# ProPrj__G__2025-08-02.net
KiCad netlist of a schematic drawn in EasyEDA Pro
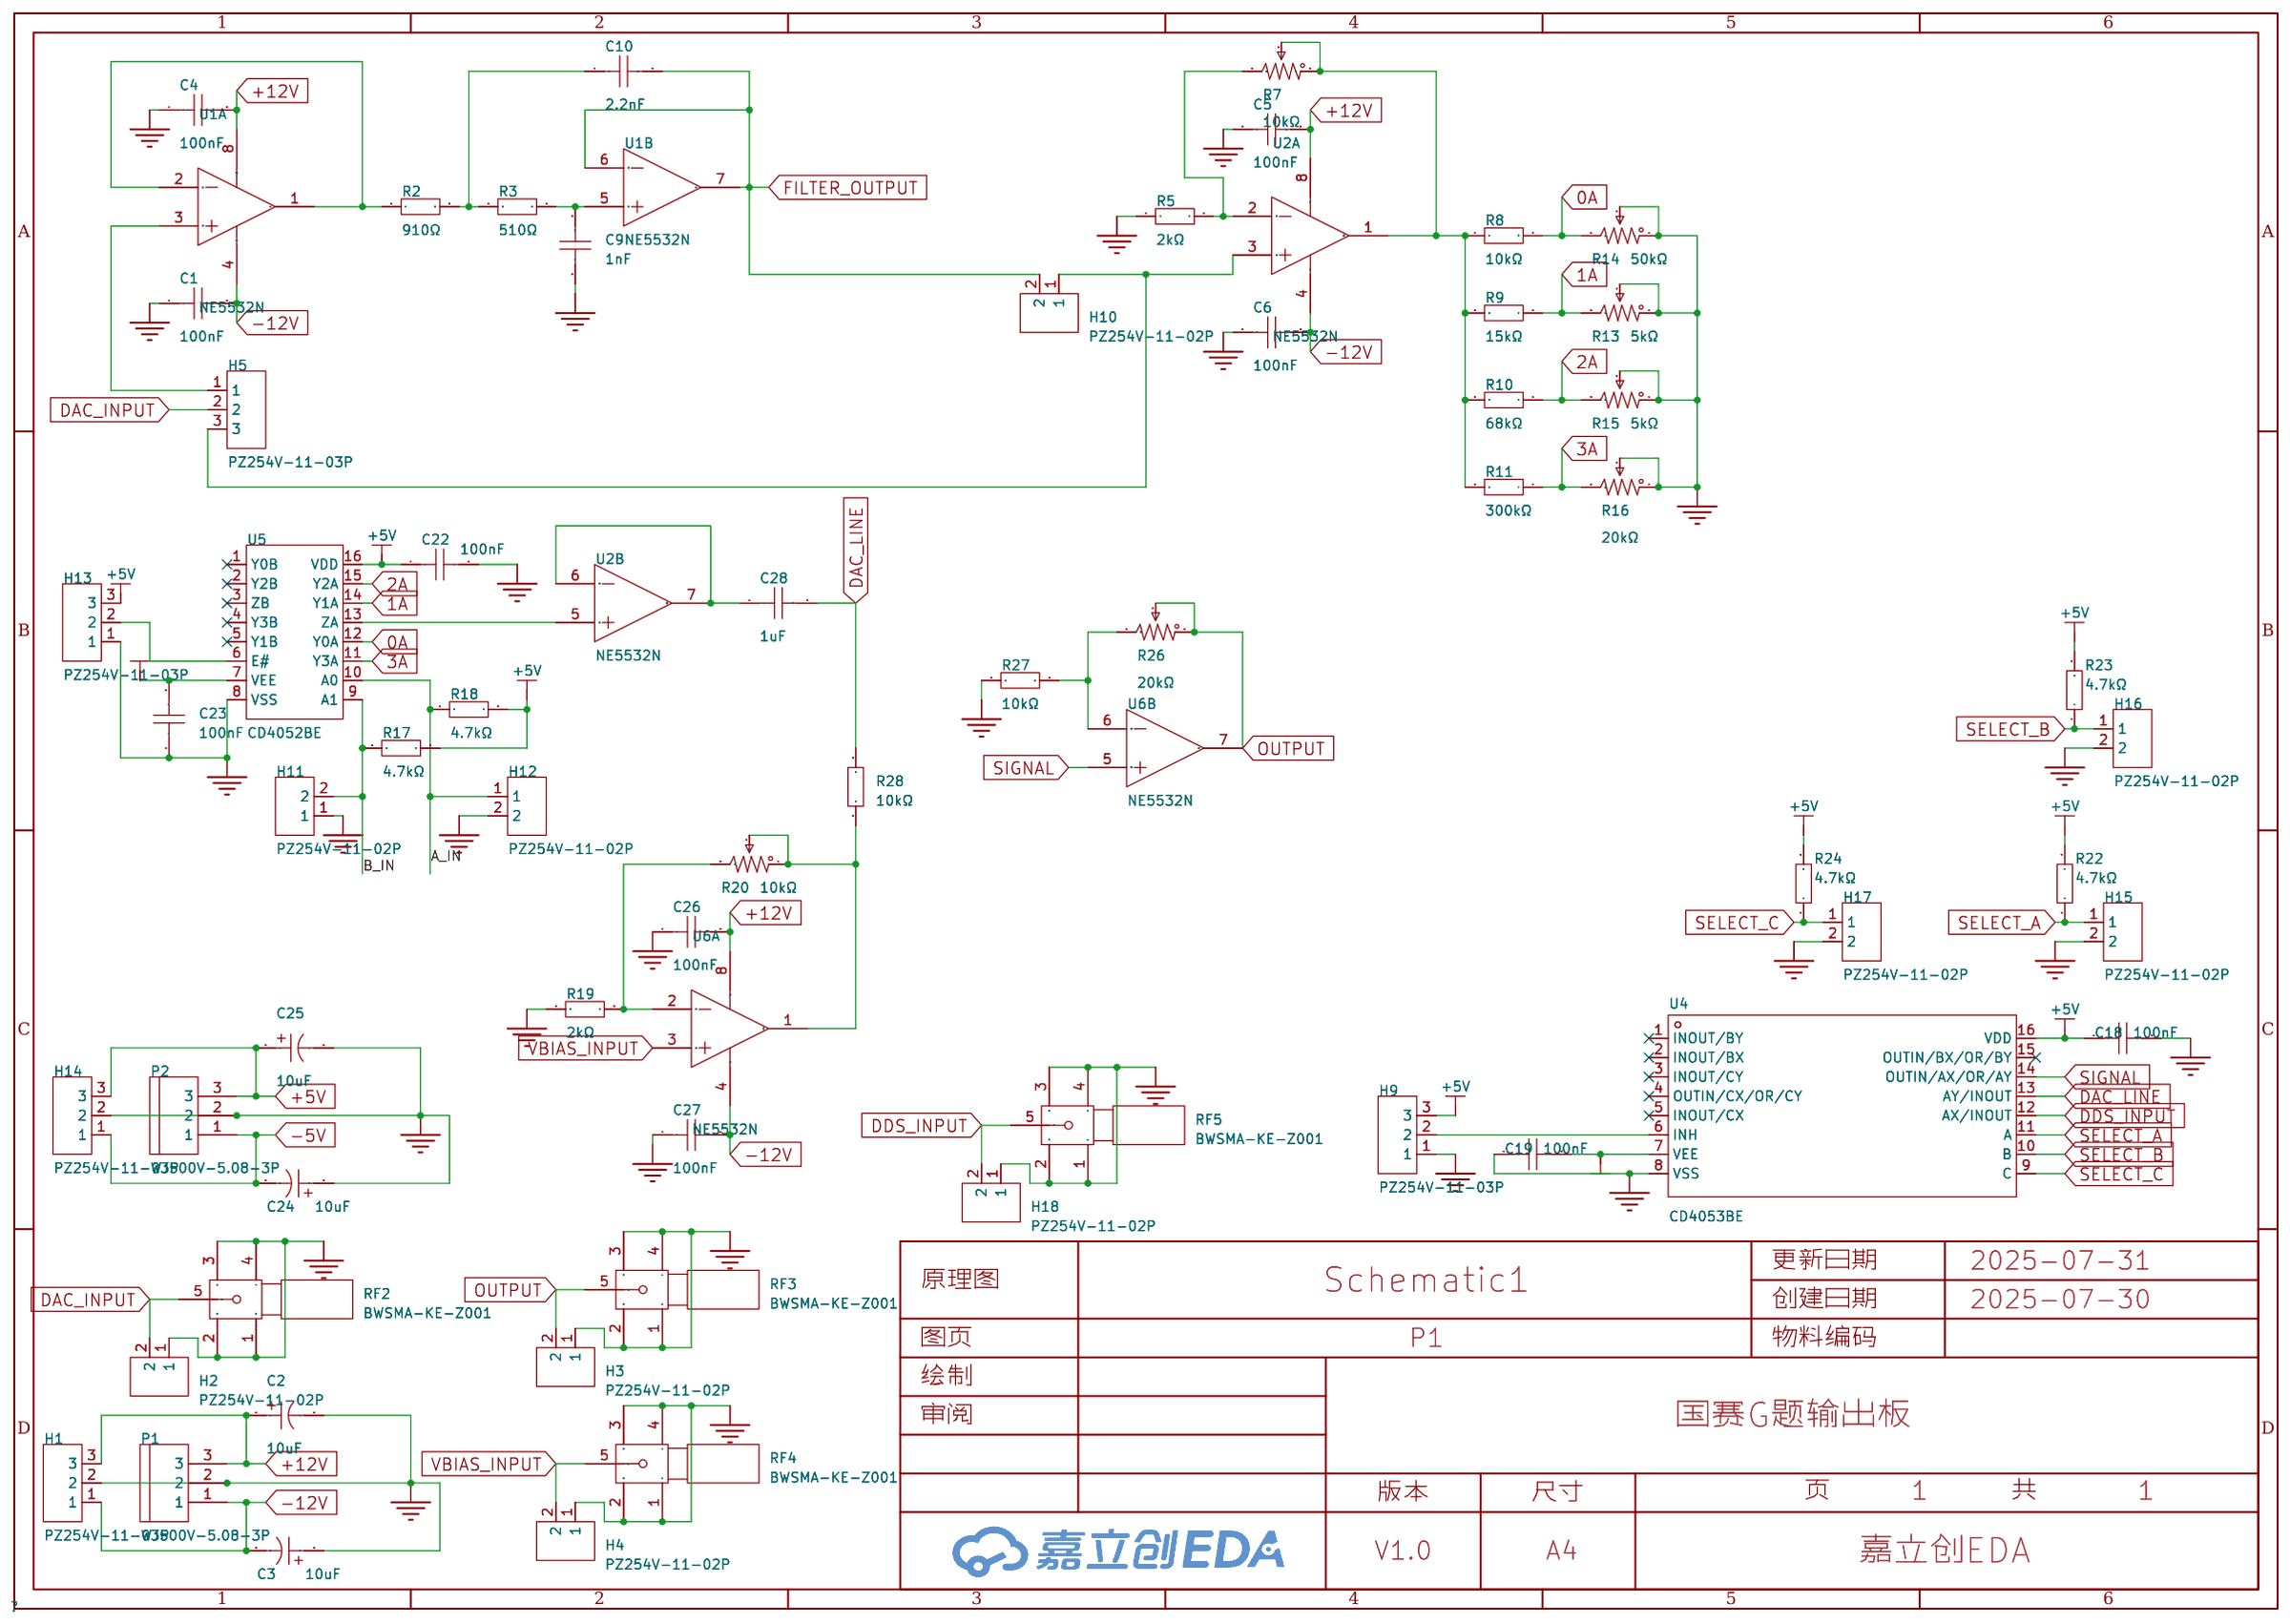
[diagram p0: schematic sheet]

(export (version "E")
  (design (tool "Eeschema 10.0.6"))
  (components
    (comp (ref "C1")
      (value "100nF")
      (footprint "easyedapro:CAP-TH_L5.8-W2.4-P2.54-D0.6")
      (description "容值:100nF;精度:-20%~+80%;额定电压:50V;温度系数:Y5V;")
      (fields
        (field (name "Manufacturer Part") "CC1H104ZA1ED3F5P1100")
        (field (name "Manufacturer") "Dersonic(德尔创)")
      )
      (libsource (lib "easyedapro") (part "CC1H104ZA1ED3F5P1100"))
    )
    (comp (ref "C2")
      (value "10uF")
      (fields (field (name "Manufacturer Part") "ERG450V10M10x16") (field (name "Manufacturer") "捷而瑞"))
      (libsource (lib "easyedapro") (part "ERG25V10M5X11"))
    )
    (comp (ref "C3")
      (value "10uF")
      (fields (field (name "Manufacturer Part") "ERG450V10M10x16") (field (name "Manufacturer") "捷而瑞"))
      (libsource (lib "easyedapro") (part "ERG25V10M5X11"))
    )
    (comp (ref "C4")
      (value "100nF")
      (footprint "easyedapro:CAP-TH_L5.8-W2.4-P2.54-D0.6")
      (description "容值:100nF;精度:-20%~+80%;额定电压:50V;温度系数:Y5V;")
      (fields
        (field (name "Manufacturer Part") "CC1H104ZA1ED3F5P1100")
        (field (name "Manufacturer") "Dersonic(德尔创)")
      )
      (libsource (lib "easyedapro") (part "CC1H104ZA1ED3F5P1100"))
    )
    (comp (ref "C5")
      (value "100nF")
      (footprint "easyedapro:CAP-TH_L5.8-W2.4-P2.54-D0.6")
      (description "容值:100nF;精度:-20%~+80%;额定电压:50V;温度系数:Y5V;")
      (fields
        (field (name "Manufacturer Part") "CC1H104ZA1ED3F5P1100")
        (field (name "Manufacturer") "Dersonic(德尔创)")
      )
      (libsource (lib "easyedapro") (part "CC1H104ZA1ED3F5P1100"))
    )
    (comp (ref "C6")
      (value "100nF")
      (footprint "easyedapro:CAP-TH_L5.8-W2.4-P2.54-D0.6")
      (description "容值:100nF;精度:-20%~+80%;额定电压:50V;温度系数:Y5V;")
      (fields
        (field (name "Manufacturer Part") "CC1H104ZA1ED3F5P1100")
        (field (name "Manufacturer") "Dersonic(德尔创)")
      )
      (libsource (lib "easyedapro") (part "CC1H104ZA1ED3F5P1100"))
    )
    (comp (ref "C9")
      (value "1nF")
      (footprint "easyedapro:CAP-TH_L6.8-W2.6-P5.08-D0.6-S2.1")
      (description "容值:1nF;精度:±10%;额定电压:2kV;温度系数:Y5P;")
      (fields
        (field (name "Manufacturer Part") "CC3D102KC2IEB46U31MF")
        (field (name "Manufacturer") "Dersonic(德尔创)")
      )
      (libsource (lib "easyedapro") (part "CC3D102KC2IEB46U31MF"))
    )
    (comp (ref "C10")
      (value "2.2nF")
      (footprint "easyedapro:CAP-TH_L6.0-W3.0-P5.00-D1.0")
      (description "容值:2.2nF;精度:±20%;额定电压:2kV;温度系数:Y5V;")
      (fields (field (name "Manufacturer Part") "R06F1B222MN0B0S0N0") (field (name "Manufacturer") "STE(松田)"))
      (libsource (lib "easyedapro") (part "R06F1B222MN0B0S0N0"))
    )
    (comp (ref "C18")
      (value "100nF")
      (footprint "easyedapro:CAP-TH_L5.0-W2.5-P5.00-D1.0")
      (description "容值:100nF;精度:±20%;额定电压:50V;温度系数:Y5V;")
      (fields
        (field (name "Manufacturer Part") "CC1H104MC1FD3F6C10MF")
        (field (name "Manufacturer") "Dersonic(德尔创)")
      )
      (libsource (lib "easyedapro") (part "CC1H104MC1FD3F6C10MF"))
    )
    (comp (ref "C19")
      (value "100nF")
      (footprint "easyedapro:CAP-TH_L5.0-W2.5-P5.00-D1.0")
      (description "容值:100nF;精度:±20%;额定电压:50V;温度系数:Y5V;")
      (fields
        (field (name "Manufacturer Part") "CC1H104MC1FD3F6C10MF")
        (field (name "Manufacturer") "Dersonic(德尔创)")
      )
      (libsource (lib "easyedapro") (part "CC1H104MC1FD3F6C10MF"))
    )
    (comp (ref "C22")
      (value "100nF")
      (footprint "easyedapro:CAP-TH_L5.8-W2.4-P2.54-D0.6")
      (description "容值:100nF;精度:-20%~+80%;额定电压:50V;温度系数:Y5V;")
      (fields
        (field (name "Manufacturer Part") "CC1H104ZA1ED3F5P1100")
        (field (name "Manufacturer") "Dersonic(德尔创)")
      )
      (libsource (lib "easyedapro") (part "CC1H104ZA1ED3F5P1100"))
    )
    (comp (ref "C23")
      (value "100nF")
      (footprint "easyedapro:CAP-TH_L5.8-W2.4-P2.54-D0.6")
      (description "容值:100nF;精度:-20%~+80%;额定电压:50V;温度系数:Y5V;")
      (fields
        (field (name "Manufacturer Part") "CC1H104ZA1ED3F5P1100")
        (field (name "Manufacturer") "Dersonic(德尔创)")
      )
      (libsource (lib "easyedapro") (part "CC1H104ZA1ED3F5P1100"))
    )
    (comp (ref "C24")
      (value "10uF")
      (fields (field (name "Manufacturer Part") "ERG450V10M10x16") (field (name "Manufacturer") "捷而瑞"))
      (libsource (lib "easyedapro") (part "ERG25V10M5X11"))
    )
    (comp (ref "C25")
      (value "10uF")
      (fields (field (name "Manufacturer Part") "ERG450V10M10x16") (field (name "Manufacturer") "捷而瑞"))
      (libsource (lib "easyedapro") (part "ERG25V10M5X11"))
    )
    (comp (ref "C26")
      (value "100nF")
      (footprint "easyedapro:CAP-TH_L5.8-W2.4-P2.54-D0.6")
      (description "容值:100nF;精度:-20%~+80%;额定电压:50V;温度系数:Y5V;")
      (fields
        (field (name "Manufacturer Part") "CC1H104ZA1ED3F5P1100")
        (field (name "Manufacturer") "Dersonic(德尔创)")
      )
      (libsource (lib "easyedapro") (part "CC1H104ZA1ED3F5P1100"))
    )
    (comp (ref "C27")
      (value "100nF")
      (footprint "easyedapro:CAP-TH_L5.8-W2.4-P2.54-D0.6")
      (description "容值:100nF;精度:-20%~+80%;额定电压:50V;温度系数:Y5V;")
      (fields
        (field (name "Manufacturer Part") "CC1H104ZA1ED3F5P1100")
        (field (name "Manufacturer") "Dersonic(德尔创)")
      )
      (libsource (lib "easyedapro") (part "CC1H104ZA1ED3F5P1100"))
    )
    (comp (ref "C28")
      (value "1uF")
      (footprint "easyedapro:CAP-TH_L5.5-W3.5-P5.00-D1.2")
      (description "容值:1uF;精度:±10%;额定电压:50V;温度系数:X7R;")
      (fields (field (name "Manufacturer Part") "FK26X7R1H105KRE06") (field (name "Manufacturer") "TDK"))
      (libsource (lib "easyedapro") (part "FK26X7R1H105KRE06"))
    )
    (comp (ref "H1")
      (value "PZ254V-11-03P")
      (footprint "easyedapro:HDR-TH_3P-P2.54-V-M")
      (fields (field (name "Manufacturer") "XFCN(兴飞)"))
      (libsource (lib "easyedapro") (part "PZ254V-11-03P_C2937625"))
    )
    (comp (ref "H2")
      (value "PZ254V-11-02P")
      (footprint "easyedapro:HDR-TH_2P-P2.54-V-M")
      (fields (field (name "Manufacturer") "XFCN(兴飞)"))
      (libsource (lib "easyedapro") (part "PZ254V-11-02P"))
    )
    (comp (ref "H3")
      (value "PZ254V-11-02P")
      (footprint "easyedapro:HDR-TH_2P-P2.54-V-M")
      (fields (field (name "Manufacturer") "XFCN(兴飞)"))
      (libsource (lib "easyedapro") (part "PZ254V-11-02P"))
    )
    (comp (ref "H4")
      (value "PZ254V-11-02P")
      (footprint "easyedapro:HDR-TH_2P-P2.54-V-M")
      (fields (field (name "Manufacturer") "XFCN(兴飞)"))
      (libsource (lib "easyedapro") (part "PZ254V-11-02P"))
    )
    (comp (ref "H5")
      (value "PZ254V-11-03P")
      (footprint "easyedapro:HDR-TH_3P-P2.54-V-M")
      (fields (field (name "Manufacturer") "XFCN(兴飞)"))
      (libsource (lib "easyedapro") (part "PZ254V-11-03P_C2937625"))
    )
    (comp (ref "H9")
      (value "PZ254V-11-03P")
      (footprint "easyedapro:HDR-TH_3P-P2.54-V-M")
      (fields (field (name "Manufacturer") "XFCN(兴飞)"))
      (libsource (lib "easyedapro") (part "PZ254V-11-03P_C2937625"))
    )
    (comp (ref "H10")
      (value "PZ254V-11-02P")
      (footprint "easyedapro:HDR-TH_2P-P2.54-V-M")
      (fields (field (name "Manufacturer") "XFCN(兴飞)"))
      (libsource (lib "easyedapro") (part "PZ254V-11-02P"))
    )
    (comp (ref "H11")
      (value "PZ254V-11-02P")
      (footprint "easyedapro:HDR-TH_2P-P2.54-V-M")
      (fields (field (name "Manufacturer") "XFCN(兴飞)"))
      (libsource (lib "easyedapro") (part "PZ254V-11-02P"))
    )
    (comp (ref "H12")
      (value "PZ254V-11-02P")
      (footprint "easyedapro:HDR-TH_2P-P2.54-V-M")
      (fields (field (name "Manufacturer") "XFCN(兴飞)"))
      (libsource (lib "easyedapro") (part "PZ254V-11-02P"))
    )
    (comp (ref "H13")
      (value "PZ254V-11-03P")
      (footprint "easyedapro:HDR-TH_3P-P2.54-V-M")
      (fields (field (name "Manufacturer") "XFCN(兴飞)"))
      (libsource (lib "easyedapro") (part "PZ254V-11-03P_C2937625"))
    )
    (comp (ref "H14")
      (value "PZ254V-11-03P")
      (footprint "easyedapro:HDR-TH_3P-P2.54-V-M")
      (fields (field (name "Manufacturer") "XFCN(兴飞)"))
      (libsource (lib "easyedapro") (part "PZ254V-11-03P_C2937625"))
    )
    (comp (ref "H15")
      (value "PZ254V-11-02P")
      (footprint "easyedapro:HDR-TH_2P-P2.54-V-M")
      (fields (field (name "Manufacturer") "XFCN(兴飞)"))
      (libsource (lib "easyedapro") (part "PZ254V-11-02P"))
    )
    (comp (ref "H16")
      (value "PZ254V-11-02P")
      (footprint "easyedapro:HDR-TH_2P-P2.54-V-M")
      (fields (field (name "Manufacturer") "XFCN(兴飞)"))
      (libsource (lib "easyedapro") (part "PZ254V-11-02P"))
    )
    (comp (ref "H17")
      (value "PZ254V-11-02P")
      (footprint "easyedapro:HDR-TH_2P-P2.54-V-M")
      (fields (field (name "Manufacturer") "XFCN(兴飞)"))
      (libsource (lib "easyedapro") (part "PZ254V-11-02P"))
    )
    (comp (ref "H18")
      (value "PZ254V-11-02P")
      (footprint "easyedapro:HDR-TH_2P-P2.54-V-M")
      (fields (field (name "Manufacturer") "XFCN(兴飞)"))
      (libsource (lib "easyedapro") (part "PZ254V-11-02P"))
    )
    (comp (ref "P1")
      (value "WJ500V-5.08-3P")
      (footprint "easyedapro:CONN-TH_3P-P5.00_WJ500V-5.08-3P")
      (fields (field (name "Manufacturer") "KANGNEX(康奈克斯电气)"))
      (libsource (lib "easyedapro") (part "WJ500V-5.08-3P-14-00A"))
    )
    (comp (ref "P2")
      (value "WJ500V-5.08-3P")
      (footprint "easyedapro:CONN-TH_3P-P5.00_WJ500V-5.08-3P")
      (fields (field (name "Manufacturer") "KANGNEX(康奈克斯电气)"))
      (libsource (lib "easyedapro") (part "WJ500V-5.08-3P-14-00A"))
    )
    (comp (ref "R2")
      (value "910Ω")
      (footprint "easyedapro:Res_1/8W")
      (libsource (lib "easyedapro") (part "电阻"))
    )
    (comp (ref "R3")
      (value "510Ω")
      (footprint "easyedapro:Res_1/8W")
      (libsource (lib "easyedapro") (part "电阻"))
    )
    (comp (ref "R5")
      (value "2kΩ")
      (footprint "easyedapro:Res_1/8W")
      (libsource (lib "easyedapro") (part "电阻"))
    )
    (comp (ref "R7")
      (value "10kΩ")
      (footprint "easyedapro:RES-ADJ-TH_3P-L10.0-W10.0-P2.50-L")
      (description "阻值:10kΩ;精度:±10%;")
      (fields (field (name "Manufacturer Part") "3296W-1-103") (field (name "Manufacturer") "BOCHEN(博晨)"))
      (libsource (lib "easyedapro") (part "3296W-1-103"))
    )
    (comp (ref "R8")
      (value "10kΩ")
      (footprint "easyedapro:Res_1/8W")
      (libsource (lib "easyedapro") (part "电阻"))
    )
    (comp (ref "R9")
      (value "15kΩ")
      (footprint "easyedapro:Res_1/8W")
      (libsource (lib "easyedapro") (part "电阻"))
    )
    (comp (ref "R10")
      (value "68kΩ")
      (footprint "easyedapro:Res_1/8W")
      (libsource (lib "easyedapro") (part "电阻"))
    )
    (comp (ref "R11")
      (value "300kΩ")
      (footprint "easyedapro:Res_1/8W")
      (libsource (lib "easyedapro") (part "电阻"))
    )
    (comp (ref "R13")
      (value "5kΩ")
      (footprint "easyedapro:RES-ADJ-TH_3P-L9.5-W4.85-P2.50-BL-BS")
      (description "阻值:5kΩ;精度:±10%;")
      (fields (field (name "Manufacturer Part") "3296W-1-502") (field (name "Manufacturer") "BOCHEN(博晨)"))
      (libsource (lib "easyedapro") (part "3296W-1-502"))
    )
    (comp (ref "R14")
      (value "50kΩ")
      (footprint "easyedapro:RES-ADJ-TH_3P-L9.5-W4.85-P2.50-BL-BS")
      (description "阻值:50kΩ;精度:±10%;")
      (fields (field (name "Manufacturer Part") "3296W-1-503") (field (name "Manufacturer") "BOCHEN(博晨)"))
      (libsource (lib "easyedapro") (part "3296W-1-503"))
    )
    (comp (ref "R15")
      (value "5kΩ")
      (footprint "easyedapro:RES-ADJ-TH_3P-L9.5-W4.85-P2.50-BL-BS")
      (description "阻值:5kΩ;精度:±10%;")
      (fields (field (name "Manufacturer Part") "3296W-1-502") (field (name "Manufacturer") "BOCHEN(博晨)"))
      (libsource (lib "easyedapro") (part "3296W-1-502"))
    )
    (comp (ref "R16")
      (value "20kΩ")
      (footprint "easyedapro:RES-ADJ-TH_3P-L10.0-W10.0-P2.50-BL-BS")
      (description "阻值:20kΩ;精度:±10%;")
      (fields (field (name "Manufacturer Part") "3296W-1-203") (field (name "Manufacturer") "BOCHEN(博晨)"))
      (libsource (lib "easyedapro") (part "3296W-1-203"))
    )
    (comp (ref "R17")
      (value "4.7kΩ")
      (footprint "easyedapro:Res_1/8W")
      (libsource (lib "easyedapro") (part "电阻"))
    )
    (comp (ref "R18")
      (value "4.7kΩ")
      (footprint "easyedapro:Res_1/8W")
      (libsource (lib "easyedapro") (part "电阻"))
    )
    (comp (ref "R19")
      (value "2kΩ")
      (footprint "easyedapro:Res_1/8W")
      (libsource (lib "easyedapro") (part "电阻"))
    )
    (comp (ref "R20")
      (value "10kΩ")
      (footprint "easyedapro:RES-ADJ-TH_3P-L10.0-W10.0-P2.50-L")
      (description "阻值:10kΩ;精度:±10%;")
      (fields (field (name "Manufacturer Part") "3296W-1-103") (field (name "Manufacturer") "BOCHEN(博晨)"))
      (libsource (lib "easyedapro") (part "3296W-1-103"))
    )
    (comp (ref "R22")
      (value "4.7kΩ")
      (footprint "easyedapro:Res_1/8W")
      (libsource (lib "easyedapro") (part "电阻"))
    )
    (comp (ref "R23")
      (value "4.7kΩ")
      (footprint "easyedapro:Res_1/8W")
      (libsource (lib "easyedapro") (part "电阻"))
    )
    (comp (ref "R24")
      (value "4.7kΩ")
      (footprint "easyedapro:Res_1/8W")
      (libsource (lib "easyedapro") (part "电阻"))
    )
    (comp (ref "R26")
      (value "20kΩ")
      (footprint "easyedapro:RES-ADJ-TH_3P-L10.0-W10.0-P2.50-BL-BS")
      (description "阻值:20kΩ;精度:±10%;")
      (fields (field (name "Manufacturer Part") "3296W-1-203") (field (name "Manufacturer") "BOCHEN(博晨)"))
      (libsource (lib "easyedapro") (part "3296W-1-203"))
    )
    (comp (ref "R27")
      (value "10kΩ")
      (footprint "easyedapro:Res_1/8W")
      (libsource (lib "easyedapro") (part "电阻"))
    )
    (comp (ref "R28")
      (value "10kΩ")
      (footprint "easyedapro:Res_1/8W")
      (libsource (lib "easyedapro") (part "电阻"))
    )
    (comp (ref "RF2")
      (value "BWSMA-KE-Z001")
      (footprint "easyedapro:SMA-TH_BWSMA-KE-Z001")
      (fields (field (name "Manufacturer") "BAT WIRELESS(蝙蝠无线)"))
      (libsource (lib "easyedapro") (part "BWSMA-KE-Z001"))
    )
    (comp (ref "RF3")
      (value "BWSMA-KE-Z001")
      (footprint "easyedapro:SMA-TH_BWSMA-KE-Z001")
      (fields (field (name "Manufacturer") "BAT WIRELESS(蝙蝠无线)"))
      (libsource (lib "easyedapro") (part "BWSMA-KE-Z001"))
    )
    (comp (ref "RF4")
      (value "BWSMA-KE-Z001")
      (footprint "easyedapro:SMA-TH_BWSMA-KE-Z001")
      (fields (field (name "Manufacturer") "BAT WIRELESS(蝙蝠无线)"))
      (libsource (lib "easyedapro") (part "BWSMA-KE-Z001"))
    )
    (comp (ref "RF5")
      (value "BWSMA-KE-Z001")
      (footprint "easyedapro:SMA-TH_BWSMA-KE-Z001")
      (fields (field (name "Manufacturer") "BAT WIRELESS(蝙蝠无线)"))
      (libsource (lib "easyedapro") (part "BWSMA-KE-Z001"))
    )
    (comp (ref "U1")
      (value "NE5532N")
      (footprint "easyedapro:DIP-8_L9.3-W6.4-P2.54-LS7.6-BL")
      (description "放大器数:双路;轨到轨:-;增益带宽积(GBP):10MHz;输入失调电压(Vos):5mV;压摆率(SR):11V/us;输入偏置电流(Ib):500nA;")
      (fields (field (name "Manufacturer") "HGSEMI(华冠)"))
      (libsource (lib "easyedapro") (part "NE5532N"))
    )
    (comp (ref "U2")
      (value "NE5532N")
      (footprint "easyedapro:DIP-8_L9.3-W6.4-P2.54-LS7.6-BL")
      (description "放大器数:双路;轨到轨:-;增益带宽积(GBP):10MHz;输入失调电压(Vos):5mV;压摆率(SR):11V/us;输入偏置电流(Ib):500nA;")
      (fields (field (name "Manufacturer") "HGSEMI(华冠)"))
      (libsource (lib "easyedapro") (part "NE5532N"))
    )
    (comp (ref "U4")
      (value "CD4053BE")
      (footprint "easyedapro:DIP-16_L20.3-W10.2-P2.54-LS10.2-BL")
      (description "开关电路:单刀双掷(SPDT);通道数:-;导通电阻:5Ω;")
      (fields (field (name "Manufacturer") "TI(德州仪器)"))
      (libsource (lib "easyedapro") (part "CD4053BE"))
    )
    (comp (ref "U5")
      (value "CD4052BE")
      (footprint "easyedapro:DIP-16_L20.0-W6.4-P2.54-LS7.6-BL")
      (description "开关电路:单刀四掷(SP4T);通道数:4;导通电阻:60Ω;")
      (fields (field (name "Manufacturer") "HGSEMI(华冠)"))
      (libsource (lib "easyedapro") (part "CD4052BE_C507162"))
    )
    (comp (ref "U6")
      (value "NE5532N")
      (footprint "easyedapro:DIP-8_L9.3-W6.4-P2.54-LS7.6-BL")
      (description "放大器数:双路;轨到轨:-;增益带宽积(GBP):10MHz;输入失调电压(Vos):5mV;压摆率(SR):11V/us;输入偏置电流(Ib):500nA;")
      (fields (field (name "Manufacturer") "HGSEMI(华冠)"))
      (libsource (lib "easyedapro") (part "NE5532N"))
    )
  )
  (nets
    (net (code "1") (name "+5V") (class "Default")
      (node (ref "C18") (pin "1") (pinfunction "1_1") (pintype "unspecified"))
      (node (ref "C22") (pin "1") (pinfunction "1_1") (pintype "unspecified"))
      (node (ref "C25") (pin "1") (pinfunction "1_1") (pintype "input"))
      (node (ref "H13") (pin "3") (pinfunction "3_3") (pintype "unspecified"))
      (node (ref "H14") (pin "3") (pinfunction "3_3") (pintype "unspecified"))
      (node (ref "H9") (pin "3") (pinfunction "3_3") (pintype "unspecified"))
      (node (ref "P2") (pin "3") (pinfunction "3_3") (pintype "unspecified"))
      (node (ref "R17") (pin "1") (pinfunction "1_1") (pintype "input"))
      (node (ref "R18") (pin "2") (pinfunction "2_2") (pintype "input"))
      (node (ref "R22") (pin "2") (pinfunction "2_2") (pintype "input"))
      (node (ref "R23") (pin "2") (pinfunction "2_2") (pintype "input"))
      (node (ref "R24") (pin "2") (pinfunction "2_2") (pintype "input"))
      (node (ref "U4") (pin "16") (pinfunction "VDD_16") (pintype "unspecified"))
      (node (ref "U5") (pin "16") (pinfunction "VDD_16") (pintype "unspecified"))
    )
    (net (code "2") (name "+12V") (class "Default")
      (node (ref "C2") (pin "1") (pinfunction "1_1") (pintype "input"))
      (node (ref "C26") (pin "2") (pinfunction "2_2") (pintype "unspecified"))
      (node (ref "C4") (pin "2") (pinfunction "2_2") (pintype "unspecified"))
      (node (ref "C5") (pin "2") (pinfunction "2_2") (pintype "unspecified"))
      (node (ref "H1") (pin "3") (pinfunction "3_3") (pintype "unspecified"))
      (node (ref "P1") (pin "3") (pinfunction "3_3") (pintype "unspecified"))
      (node (ref "U1") (pin "8") (pinfunction "VCC+_8") (pintype "unspecified"))
      (node (ref "U2") (pin "8") (pinfunction "VCC+_8") (pintype "unspecified"))
      (node (ref "U6") (pin "8") (pinfunction "VCC+_8") (pintype "unspecified"))
    )
    (net (code "3") (name "-5V") (class "Default")
      (node (ref "C19") (pin "2") (pinfunction "2_2") (pintype "unspecified"))
      (node (ref "C23") (pin "2") (pinfunction "2_2") (pintype "unspecified"))
      (node (ref "C24") (pin "2") (pinfunction "2_2") (pintype "input"))
      (node (ref "H14") (pin "1") (pinfunction "1_1") (pintype "unspecified"))
      (node (ref "P2") (pin "1") (pinfunction "1_1") (pintype "unspecified"))
      (node (ref "U4") (pin "7") (pinfunction "VEE_7") (pintype "unspecified"))
      (node (ref "U5") (pin "7") (pinfunction "VEE_7") (pintype "unspecified"))
    )
    (net (code "4") (name "-12V") (class "Default")
      (node (ref "C1") (pin "2") (pinfunction "2_2") (pintype "unspecified"))
      (node (ref "C27") (pin "2") (pinfunction "2_2") (pintype "unspecified"))
      (node (ref "C3") (pin "2") (pinfunction "2_2") (pintype "input"))
      (node (ref "C6") (pin "2") (pinfunction "2_2") (pintype "unspecified"))
      (node (ref "H1") (pin "1") (pinfunction "1_1") (pintype "unspecified"))
      (node (ref "P1") (pin "1") (pinfunction "1_1") (pintype "unspecified"))
      (node (ref "U1") (pin "4") (pinfunction "VCC-_4") (pintype "unspecified"))
      (node (ref "U2") (pin "4") (pinfunction "VCC-_4") (pintype "unspecified"))
      (node (ref "U6") (pin "4") (pinfunction "VCC-_4") (pintype "unspecified"))
    )
    (net (code "5") (name "/A_IN") (class "Default")
      (node (ref "H12") (pin "1") (pinfunction "1_1") (pintype "unspecified"))
      (node (ref "R18") (pin "1") (pinfunction "1_1") (pintype "input"))
      (node (ref "U5") (pin "10") (pinfunction "A0_10") (pintype "unspecified"))
    )
    (net (code "6") (name "/B_IN") (class "Default")
      (node (ref "H11") (pin "2") (pinfunction "2_2") (pintype "unspecified"))
      (node (ref "R17") (pin "2") (pinfunction "2_2") (pintype "input"))
      (node (ref "U5") (pin "9") (pinfunction "A1_9") (pintype "unspecified"))
    )
    (net (code "7") (name "0A") (class "Default")
      (node (ref "R14") (pin "3") (pinfunction "3_3") (pintype "unspecified"))
      (node (ref "R8") (pin "2") (pinfunction "2_2") (pintype "input"))
      (node (ref "U5") (pin "12") (pinfunction "Y0A_12") (pintype "unspecified"))
    )
    (net (code "8") (name "1A") (class "Default")
      (node (ref "R13") (pin "3") (pinfunction "3_3") (pintype "unspecified"))
      (node (ref "R9") (pin "1") (pinfunction "1_1") (pintype "input"))
      (node (ref "U5") (pin "14") (pinfunction "Y1A_14") (pintype "unspecified"))
    )
    (net (code "9") (name "2A") (class "Default")
      (node (ref "R10") (pin "1") (pinfunction "1_1") (pintype "input"))
      (node (ref "R15") (pin "3") (pinfunction "3_3") (pintype "unspecified"))
      (node (ref "U5") (pin "15") (pinfunction "Y2A_15") (pintype "unspecified"))
    )
    (net (code "10") (name "3A") (class "Default")
      (node (ref "R11") (pin "1") (pinfunction "1_1") (pintype "input"))
      (node (ref "R16") (pin "3") (pinfunction "3_3") (pintype "unspecified"))
      (node (ref "U5") (pin "11") (pinfunction "Y3A_11") (pintype "unspecified"))
    )
    (net (code "11") (name "DAC_INPUT") (class "Default")
      (node (ref "H2") (pin "2") (pinfunction "2_2") (pintype "unspecified"))
      (node (ref "H5") (pin "2") (pinfunction "2_2") (pintype "unspecified"))
      (node (ref "RF2") (pin "5") (pinfunction "5_5") (pintype "unspecified"))
    )
    (net (code "12") (name "DAC_LINE") (class "Default")
      (node (ref "C28") (pin "2") (pinfunction "2_2") (pintype "unspecified"))
      (node (ref "R28") (pin "2") (pinfunction "2_2") (pintype "input"))
      (node (ref "U4") (pin "13") (pinfunction "AY/INOUT_13") (pintype "unspecified"))
    )
    (net (code "13") (name "DDS_INPUT") (class "Default")
      (node (ref "H18") (pin "2") (pinfunction "2_2") (pintype "unspecified"))
      (node (ref "RF5") (pin "5") (pinfunction "5_5") (pintype "unspecified"))
      (node (ref "U4") (pin "12") (pinfunction "AX/INOUT_12") (pintype "unspecified"))
    )
    (net (code "14") (name "FILTER_OUTPUT") (class "Default")
      (node (ref "C10") (pin "2") (pinfunction "2_2") (pintype "unspecified"))
      (node (ref "H10") (pin "2") (pinfunction "2_2") (pintype "unspecified"))
      (node (ref "U1") (pin "6") (pinfunction "IN2-_6") (pintype "unspecified"))
      (node (ref "U1") (pin "7") (pinfunction "OUT2_7") (pintype "output"))
    )
    (net (code "15") (name "GND") (class "Default")
      (node (ref "C1") (pin "1") (pinfunction "1_1") (pintype "unspecified"))
      (node (ref "C18") (pin "2") (pinfunction "2_2") (pintype "unspecified"))
      (node (ref "C19") (pin "1") (pinfunction "1_1") (pintype "unspecified"))
      (node (ref "C2") (pin "2") (pinfunction "2_2") (pintype "input"))
      (node (ref "C22") (pin "2") (pinfunction "2_2") (pintype "unspecified"))
      (node (ref "C23") (pin "1") (pinfunction "1_1") (pintype "unspecified"))
      (node (ref "C24") (pin "1") (pinfunction "1_1") (pintype "input"))
      (node (ref "C25") (pin "2") (pinfunction "2_2") (pintype "input"))
      (node (ref "C26") (pin "1") (pinfunction "1_1") (pintype "unspecified"))
      (node (ref "C27") (pin "1") (pinfunction "1_1") (pintype "unspecified"))
      (node (ref "C3") (pin "1") (pinfunction "1_1") (pintype "input"))
      (node (ref "C4") (pin "1") (pinfunction "1_1") (pintype "unspecified"))
      (node (ref "C5") (pin "1") (pinfunction "1_1") (pintype "unspecified"))
      (node (ref "C6") (pin "1") (pinfunction "1_1") (pintype "unspecified"))
      (node (ref "C9") (pin "1") (pinfunction "1_1") (pintype "unspecified"))
      (node (ref "H1") (pin "2") (pinfunction "2_2") (pintype "unspecified"))
      (node (ref "H11") (pin "1") (pinfunction "1_1") (pintype "unspecified"))
      (node (ref "H12") (pin "2") (pinfunction "2_2") (pintype "unspecified"))
      (node (ref "H13") (pin "1") (pinfunction "1_1") (pintype "unspecified"))
      (node (ref "H14") (pin "2") (pinfunction "2_2") (pintype "unspecified"))
      (node (ref "H15") (pin "2") (pinfunction "2_2") (pintype "unspecified"))
      (node (ref "H16") (pin "2") (pinfunction "2_2") (pintype "unspecified"))
      (node (ref "H17") (pin "2") (pinfunction "2_2") (pintype "unspecified"))
      (node (ref "H18") (pin "1") (pinfunction "1_1") (pintype "unspecified"))
      (node (ref "H2") (pin "1") (pinfunction "1_1") (pintype "unspecified"))
      (node (ref "H3") (pin "1") (pinfunction "1_1") (pintype "unspecified"))
      (node (ref "H4") (pin "1") (pinfunction "1_1") (pintype "unspecified"))
      (node (ref "H9") (pin "1") (pinfunction "1_1") (pintype "unspecified"))
      (node (ref "P1") (pin "2") (pinfunction "2_2") (pintype "unspecified"))
      (node (ref "P2") (pin "2") (pinfunction "2_2") (pintype "unspecified"))
      (node (ref "R13") (pin "1") (pinfunction "1_1") (pintype "unspecified"))
      (node (ref "R13") (pin "2") (pinfunction "2_2") (pintype "unspecified"))
      (node (ref "R14") (pin "1") (pinfunction "1_1") (pintype "unspecified"))
      (node (ref "R14") (pin "2") (pinfunction "2_2") (pintype "unspecified"))
      (node (ref "R15") (pin "1") (pinfunction "1_1") (pintype "unspecified"))
      (node (ref "R15") (pin "2") (pinfunction "2_2") (pintype "unspecified"))
      (node (ref "R16") (pin "1") (pinfunction "1_1") (pintype "unspecified"))
      (node (ref "R16") (pin "2") (pinfunction "2_2") (pintype "unspecified"))
      (node (ref "R19") (pin "1") (pinfunction "1_1") (pintype "input"))
      (node (ref "R27") (pin "1") (pinfunction "1_1") (pintype "input"))
      (node (ref "R5") (pin "1") (pinfunction "1_1") (pintype "input"))
      (node (ref "RF2") (pin "1") (pinfunction "1_1") (pintype "unspecified"))
      (node (ref "RF2") (pin "2") (pinfunction "2_2") (pintype "unspecified"))
      (node (ref "RF2") (pin "3") (pinfunction "3_3") (pintype "unspecified"))
      (node (ref "RF2") (pin "4") (pinfunction "4_4") (pintype "unspecified"))
      (node (ref "RF3") (pin "1") (pinfunction "1_1") (pintype "unspecified"))
      (node (ref "RF3") (pin "2") (pinfunction "2_2") (pintype "unspecified"))
      (node (ref "RF3") (pin "3") (pinfunction "3_3") (pintype "unspecified"))
      (node (ref "RF3") (pin "4") (pinfunction "4_4") (pintype "unspecified"))
      (node (ref "RF4") (pin "1") (pinfunction "1_1") (pintype "unspecified"))
      (node (ref "RF4") (pin "2") (pinfunction "2_2") (pintype "unspecified"))
      (node (ref "RF4") (pin "3") (pinfunction "3_3") (pintype "unspecified"))
      (node (ref "RF4") (pin "4") (pinfunction "4_4") (pintype "unspecified"))
      (node (ref "RF5") (pin "1") (pinfunction "1_1") (pintype "unspecified"))
      (node (ref "RF5") (pin "2") (pinfunction "2_2") (pintype "unspecified"))
      (node (ref "RF5") (pin "3") (pinfunction "3_3") (pintype "unspecified"))
      (node (ref "RF5") (pin "4") (pinfunction "4_4") (pintype "unspecified"))
      (node (ref "U4") (pin "8") (pinfunction "VSS_8") (pintype "unspecified"))
      (node (ref "U5") (pin "8") (pinfunction "VSS_8") (pintype "unspecified"))
    )
    (net (code "16") (name "Net-(C10-Pad1)") (class "Default")
      (node (ref "C10") (pin "1") (pinfunction "1_1") (pintype "unspecified"))
      (node (ref "R2") (pin "2") (pinfunction "2_2") (pintype "input"))
      (node (ref "R3") (pin "1") (pinfunction "1_1") (pintype "input"))
    )
    (net (code "17") (name "Net-(U1A-IN1+)") (class "Default")
      (node (ref "H5") (pin "1") (pinfunction "1_1") (pintype "unspecified"))
      (node (ref "U1") (pin "3") (pinfunction "IN1+_3") (pintype "unspecified"))
    )
    (net (code "18") (name "Net-(U1A-IN1-)") (class "Default")
      (node (ref "R2") (pin "1") (pinfunction "1_1") (pintype "input"))
      (node (ref "U1") (pin "1") (pinfunction "OUT1_1") (pintype "output"))
      (node (ref "U1") (pin "2") (pinfunction "IN1-_2") (pintype "unspecified"))
    )
    (net (code "19") (name "Net-(U1B-IN2+)") (class "Default")
      (node (ref "C9") (pin "2") (pinfunction "2_2") (pintype "unspecified"))
      (node (ref "R3") (pin "2") (pinfunction "2_2") (pintype "input"))
      (node (ref "U1") (pin "5") (pinfunction "IN2+_5") (pintype "unspecified"))
    )
    (net (code "20") (name "Net-(U2A-IN1+)") (class "Default")
      (node (ref "H10") (pin "1") (pinfunction "1_1") (pintype "unspecified"))
      (node (ref "H5") (pin "3") (pinfunction "3_3") (pintype "unspecified"))
      (node (ref "U2") (pin "3") (pinfunction "IN1+_3") (pintype "unspecified"))
    )
    (net (code "21") (name "Net-(U2A-IN1-)") (class "Default")
      (node (ref "R5") (pin "2") (pinfunction "2_2") (pintype "input"))
      (node (ref "R7") (pin "3") (pinfunction "3_3") (pintype "unspecified"))
      (node (ref "U2") (pin "2") (pinfunction "IN1-_2") (pintype "unspecified"))
    )
    (net (code "22") (name "Net-(U2A-OUT1)") (class "Default")
      (node (ref "R10") (pin "2") (pinfunction "2_2") (pintype "input"))
      (node (ref "R11") (pin "2") (pinfunction "2_2") (pintype "input"))
      (node (ref "R7") (pin "1") (pinfunction "1_1") (pintype "unspecified"))
      (node (ref "R7") (pin "2") (pinfunction "2_2") (pintype "unspecified"))
      (node (ref "R8") (pin "1") (pinfunction "1_1") (pintype "input"))
      (node (ref "R9") (pin "2") (pinfunction "2_2") (pintype "input"))
      (node (ref "U2") (pin "1") (pinfunction "OUT1_1") (pintype "output"))
    )
    (net (code "23") (name "Net-(U2B-IN2+)") (class "Default")
      (node (ref "U2") (pin "5") (pinfunction "IN2+_5") (pintype "unspecified"))
      (node (ref "U5") (pin "13") (pinfunction "ZA_13") (pintype "unspecified"))
    )
    (net (code "24") (name "Net-(U2B-IN2-)") (class "Default")
      (node (ref "C28") (pin "1") (pinfunction "1_1") (pintype "unspecified"))
      (node (ref "U2") (pin "6") (pinfunction "IN2-_6") (pintype "unspecified"))
      (node (ref "U2") (pin "7") (pinfunction "OUT2_7") (pintype "output"))
    )
    (net (code "25") (name "Net-(U4-INH)") (class "Default")
      (node (ref "H9") (pin "2") (pinfunction "2_2") (pintype "unspecified"))
      (node (ref "U4") (pin "6") (pinfunction "INH_6") (pintype "unspecified"))
    )
    (net (code "26") (name "Net-(U5-E#)") (class "Default")
      (node (ref "H13") (pin "2") (pinfunction "2_2") (pintype "unspecified"))
      (node (ref "U5") (pin "6") (pinfunction "E#_6") (pintype "unspecified"))
    )
    (net (code "27") (name "Net-(U6A-IN1-)") (class "Default")
      (node (ref "R19") (pin "2") (pinfunction "2_2") (pintype "input"))
      (node (ref "R20") (pin "3") (pinfunction "3_3") (pintype "unspecified"))
      (node (ref "U6") (pin "2") (pinfunction "IN1-_2") (pintype "unspecified"))
    )
    (net (code "28") (name "Net-(U6A-OUT1)") (class "Default")
      (node (ref "R20") (pin "1") (pinfunction "1_1") (pintype "unspecified"))
      (node (ref "R20") (pin "2") (pinfunction "2_2") (pintype "unspecified"))
      (node (ref "R28") (pin "1") (pinfunction "1_1") (pintype "input"))
      (node (ref "U6") (pin "1") (pinfunction "OUT1_1") (pintype "output"))
    )
    (net (code "29") (name "Net-(U6B-IN2-)") (class "Default")
      (node (ref "R26") (pin "3") (pinfunction "3_3") (pintype "unspecified"))
      (node (ref "R27") (pin "2") (pinfunction "2_2") (pintype "input"))
      (node (ref "U6") (pin "6") (pinfunction "IN2-_6") (pintype "unspecified"))
    )
    (net (code "30") (name "OUTPUT") (class "Default")
      (node (ref "H3") (pin "2") (pinfunction "2_2") (pintype "unspecified"))
      (node (ref "R26") (pin "1") (pinfunction "1_1") (pintype "unspecified"))
      (node (ref "R26") (pin "2") (pinfunction "2_2") (pintype "unspecified"))
      (node (ref "RF3") (pin "5") (pinfunction "5_5") (pintype "unspecified"))
      (node (ref "U6") (pin "7") (pinfunction "OUT2_7") (pintype "output"))
    )
    (net (code "31") (name "SELECT_A") (class "Default")
      (node (ref "H15") (pin "1") (pinfunction "1_1") (pintype "unspecified"))
      (node (ref "R22") (pin "1") (pinfunction "1_1") (pintype "input"))
      (node (ref "U4") (pin "11") (pinfunction "A_11") (pintype "unspecified"))
    )
    (net (code "32") (name "SELECT_B") (class "Default")
      (node (ref "H16") (pin "1") (pinfunction "1_1") (pintype "unspecified"))
      (node (ref "R23") (pin "1") (pinfunction "1_1") (pintype "input"))
      (node (ref "U4") (pin "10") (pinfunction "B_10") (pintype "unspecified"))
    )
    (net (code "33") (name "SELECT_C") (class "Default")
      (node (ref "H17") (pin "1") (pinfunction "1_1") (pintype "unspecified"))
      (node (ref "R24") (pin "1") (pinfunction "1_1") (pintype "input"))
      (node (ref "U4") (pin "9") (pinfunction "C_9") (pintype "unspecified"))
    )
    (net (code "34") (name "SIGNAL") (class "Default")
      (node (ref "U4") (pin "14") (pinfunction "OUTIN/AX/OR/AY_14") (pintype "unspecified"))
      (node (ref "U6") (pin "5") (pinfunction "IN2+_5") (pintype "unspecified"))
    )
    (net (code "35") (name "VBIAS_INPUT") (class "Default")
      (node (ref "H4") (pin "2") (pinfunction "2_2") (pintype "unspecified"))
      (node (ref "RF4") (pin "5") (pinfunction "5_5") (pintype "unspecified"))
      (node (ref "U6") (pin "3") (pinfunction "IN1+_3") (pintype "unspecified"))
    )
    (net (code "36") (name "unconnected-(U4-INOUT{slash}BX-Pad2)") (class "Default")
      (node (ref "U4") (pin "2") (pinfunction "INOUT/BX_2") (pintype "unspecified+no_connect"))
    )
    (net (code "37") (name "unconnected-(U4-INOUT{slash}BY-Pad1)") (class "Default")
      (node (ref "U4") (pin "1") (pinfunction "INOUT/BY_1") (pintype "unspecified+no_connect"))
    )
    (net (code "38") (name "unconnected-(U4-INOUT{slash}CX-Pad5)") (class "Default")
      (node (ref "U4") (pin "5") (pinfunction "INOUT/CX_5") (pintype "unspecified+no_connect"))
    )
    (net (code "39") (name "unconnected-(U4-INOUT{slash}CY-Pad3)") (class "Default")
      (node (ref "U4") (pin "3") (pinfunction "INOUT/CY_3") (pintype "unspecified+no_connect"))
    )
    (net (code "40") (name "unconnected-(U4-OUTIN{slash}BX{slash}OR{slash}BY-Pad15)") (class "Default")
      (node (ref "U4") (pin "15") (pinfunction "OUTIN/BX/OR/BY_15") (pintype "unspecified+no_connect"))
    )
    (net (code "41") (name "unconnected-(U4-OUTIN{slash}CX{slash}OR{slash}CY-Pad4)") (class "Default")
      (node (ref "U4") (pin "4") (pinfunction "OUTIN/CX/OR/CY_4") (pintype "unspecified+no_connect"))
    )
    (net (code "42") (name "unconnected-(U5-Y0B-Pad1)") (class "Default")
      (node (ref "U5") (pin "1") (pinfunction "Y0B_1") (pintype "unspecified+no_connect"))
    )
    (net (code "43") (name "unconnected-(U5-Y1B-Pad5)") (class "Default")
      (node (ref "U5") (pin "5") (pinfunction "Y1B_5") (pintype "unspecified+no_connect"))
    )
    (net (code "44") (name "unconnected-(U5-Y2B-Pad2)") (class "Default")
      (node (ref "U5") (pin "2") (pinfunction "Y2B_2") (pintype "unspecified+no_connect"))
    )
    (net (code "45") (name "unconnected-(U5-Y3B-Pad4)") (class "Default")
      (node (ref "U5") (pin "4") (pinfunction "Y3B_4") (pintype "unspecified+no_connect"))
    )
    (net (code "46") (name "unconnected-(U5-ZB-Pad3)") (class "Default")
      (node (ref "U5") (pin "3") (pinfunction "ZB_3") (pintype "unspecified+no_connect"))
    )
  )
)
